# MISchematic.net
KiCad netlist of a schematic drawn in Altium Designer
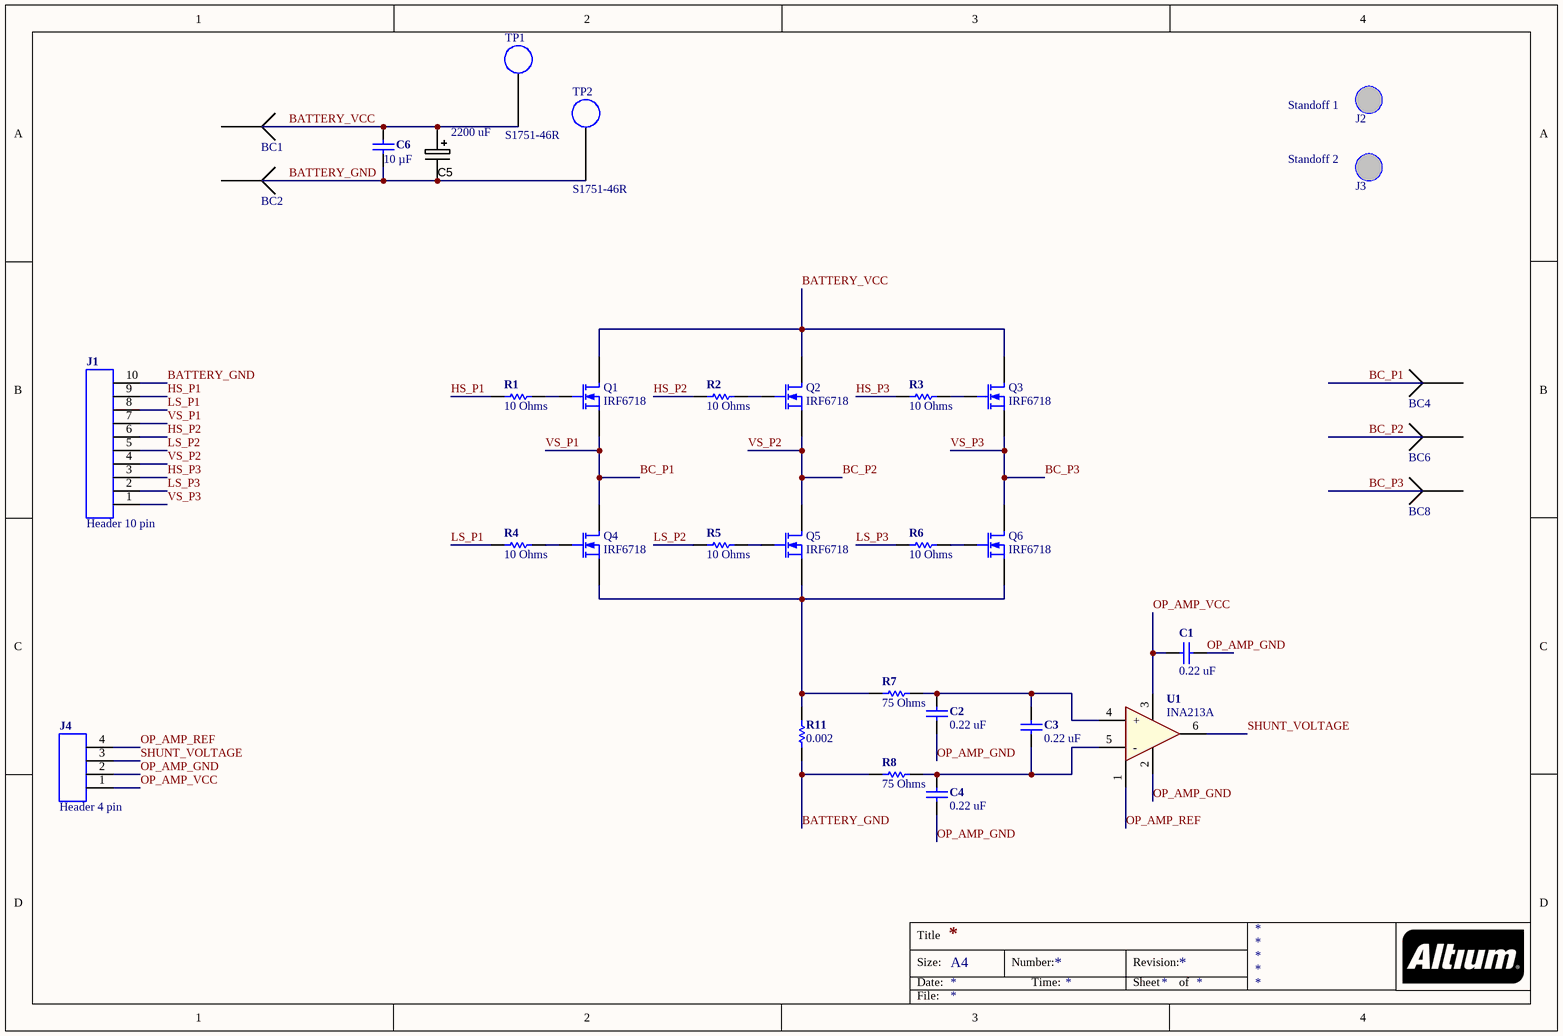
[diagram p0: MISchematic.SchDoc]

(export (version "E")
  (design (tool "Eeschema 10.0.6"))
  (components
    (comp (ref "BC1")
      (value "Bullet Connector Top")
      (footprint "BULLET_CONNECTOR_TOP")
      (description "SMD BULLET CONNECTOR")
      (libsource (lib "CarlLibrary") (part "Bullet Connector Top"))
    )
    (comp (ref "BC2")
      (value "Bullet Connector Top")
      (footprint "BULLET_CONNECTOR_TOP")
      (description "SMD BULLET CONNECTOR")
      (libsource (lib "CarlLibrary") (part "Bullet Connector Top"))
    )
    (comp (ref "BC4")
      (value "Bullet Connector Top")
      (footprint "BULLET_CONNECTOR_TOP")
      (description "SMD BULLET CONNECTOR")
      (libsource (lib "CarlLibrary") (part "Bullet Connector Top"))
    )
    (comp (ref "BC6")
      (value "Bullet Connector Top")
      (footprint "BULLET_CONNECTOR_TOP")
      (description "SMD BULLET CONNECTOR")
      (libsource (lib "CarlLibrary") (part "Bullet Connector Top"))
    )
    (comp (ref "BC8")
      (value "Bullet Connector Top")
      (footprint "BULLET_CONNECTOR_TOP")
      (description "SMD BULLET CONNECTOR")
      (libsource (lib "CarlLibrary") (part "Bullet Connector Top"))
    )
    (comp (ref "C1")
      (value "0.22 uF")
      (footprint "CAP-0805(2012)-R")
      (description "CAP CER 0.22 UF 16V 10% X7R 0805(2012)")
      (fields
        (field (name "MANUFACTURER") "Yageo")
        (field (name "MANUFACTURER PART NUMBER") "CC0805KRX7R7BB224")
      )
      (libsource (lib "CarlLibrary") (part "CAP- 0.22 uF- 16 V-CER-0805(1202)"))
    )
    (comp (ref "C2")
      (value "0.22 uF")
      (footprint "CAP-0805(2012)-R")
      (description "CAP CER 0.22 UF 16V 10% X7R 0805(2012)")
      (fields
        (field (name "MANUFACTURER") "Yageo")
        (field (name "MANUFACTURER PART NUMBER") "CC0805KRX7R7BB224")
      )
      (libsource (lib "CarlLibrary") (part "CAP- 0.22 uF- 16 V-CER-0805(1202)"))
    )
    (comp (ref "C3")
      (value "0.22 uF")
      (footprint "CAP-0805(2012)-R")
      (description "CAP CER 0.22 UF 16V 10% X7R 0805(2012)")
      (fields
        (field (name "MANUFACTURER") "Yageo")
        (field (name "MANUFACTURER PART NUMBER") "CC0805KRX7R7BB224")
      )
      (libsource (lib "CarlLibrary") (part "CAP- 0.22 uF- 16 V-CER-0805(1202)"))
    )
    (comp (ref "C4")
      (value "0.22 uF")
      (footprint "CAP-0805(2012)-R")
      (description "CAP CER 0.22 UF 16V 10% X7R 0805(2012)")
      (fields
        (field (name "MANUFACTURER") "Yageo")
        (field (name "MANUFACTURER PART NUMBER") "CC0805KRX7R7BB224")
      )
      (libsource (lib "CarlLibrary") (part "CAP- 0.22 uF- 16 V-CER-0805(1202)"))
    )
    (comp (ref "C5")
      (value "~")
      (footprint "2200uF_Rad_18x25mm")
      (description "Capacitor THT Alum Elec 2200uF 20% 50V")
      (fields (field (name "TOLERANCE") "±20%"))
      (libsource (lib "CarlLibrary") (part "CAP_2200uF_50V_THT"))
    )
    (comp (ref "C6")
      (value "10 µF")
      (footprint "CAP-1210(3225)-R")
      (description "CAP CER 10 UF 50V 10% X5R 1210")
      (fields (field (name "TOLERANCE") "±%") (field (name "MANUFACTURER") "Yageo"))
      (libsource (lib "CarlLibrary") (part "CAP- 10 uF- 50 V-CER-1210(3225)"))
    )
    (comp (ref "J1")
      (value "Header 10 pin")
      (footprint "HEADER-10-100MIL")
      (description "Header, 10pin, .1 pitch")
      (fields (field (name "MANUFACTURER") "Molex"))
      (libsource (lib "CarlLibrary") (part "CON-10Pin-100Mil"))
    )
    (comp (ref "J2")
      (value "Stand-off")
      (footprint "6-32 Threaded Standoff")
      (libsource (lib "CarlLibrary") (part "Stand-off"))
    )
    (comp (ref "J3")
      (value "Stand-off")
      (footprint "6-32 Threaded Standoff")
      (libsource (lib "CarlLibrary") (part "Stand-off"))
    )
    (comp (ref "J4")
      (value "Header 4 pin")
      (footprint "HEADER-4-100mil")
      (description "Header, 4 pin, .1 pitch")
      (libsource (lib "CarlLibrary") (part "CON-4Pin-100Mil"))
    )
    (comp (ref "Q1")
      (value "IRF6718")
      (footprint "DirectFet-7")
      (description "IRF6718L2TRPBF")
      (fields (field (name "PUBLISHER") "Altium Limited"))
      (libsource (lib "MasterLibrary") (part "IRF6718"))
    )
    (comp (ref "Q2")
      (value "IRF6718")
      (footprint "DirectFet-7")
      (description "IRF6718L2TRPBF")
      (fields (field (name "PUBLISHER") "Altium Limited"))
      (libsource (lib "MasterLibrary") (part "IRF6718"))
    )
    (comp (ref "Q3")
      (value "IRF6718")
      (footprint "DirectFet-7")
      (description "IRF6718L2TRPBF")
      (fields (field (name "PUBLISHER") "Altium Limited"))
      (libsource (lib "MasterLibrary") (part "IRF6718"))
    )
    (comp (ref "Q4")
      (value "IRF6718")
      (footprint "DirectFet-7")
      (description "IRF6718L2TRPBF")
      (fields (field (name "PUBLISHER") "Altium Limited"))
      (libsource (lib "MasterLibrary") (part "IRF6718"))
    )
    (comp (ref "Q5")
      (value "IRF6718")
      (footprint "DirectFet-7")
      (description "IRF6718L2TRPBF")
      (fields (field (name "PUBLISHER") "Altium Limited"))
      (libsource (lib "MasterLibrary") (part "IRF6718"))
    )
    (comp (ref "Q6")
      (value "IRF6718")
      (footprint "DirectFet-7")
      (description "IRF6718L2TRPBF")
      (fields (field (name "PUBLISHER") "Altium Limited"))
      (libsource (lib "MasterLibrary") (part "IRF6718"))
    )
    (comp (ref "R1")
      (value "10 Ohms")
      (footprint "R-0805(2012)-R")
      (description "RES 10 OHM 1/8W 0805 SMD")
      (fields
        (field (name "MANUFACTURER") "Yageo")
        (field (name "MANUFACTURER PART NUMBER") "RC0805FR-0710RL")
      )
      (libsource (lib "CarlLibrary") (part "R-10-125mW-0805"))
    )
    (comp (ref "R2")
      (value "10 Ohms")
      (footprint "R-0805(2012)-R")
      (description "RES 10 OHM 1/8W 0805 SMD")
      (fields
        (field (name "MANUFACTURER") "Yageo")
        (field (name "MANUFACTURER PART NUMBER") "RC0805FR-0710RL")
      )
      (libsource (lib "CarlLibrary") (part "R-10-125mW-0805"))
    )
    (comp (ref "R3")
      (value "10 Ohms")
      (footprint "R-0805(2012)-R")
      (description "RES 10 OHM 1/8W 0805 SMD")
      (fields
        (field (name "MANUFACTURER") "Yageo")
        (field (name "MANUFACTURER PART NUMBER") "RC0805FR-0710RL")
      )
      (libsource (lib "CarlLibrary") (part "R-10-125mW-0805"))
    )
    (comp (ref "R4")
      (value "10 Ohms")
      (footprint "R-0805(2012)-R")
      (description "RES 10 OHM 1/8W 0805 SMD")
      (fields
        (field (name "MANUFACTURER") "Yageo")
        (field (name "MANUFACTURER PART NUMBER") "RC0805FR-0710RL")
      )
      (libsource (lib "CarlLibrary") (part "R-10-125mW-0805"))
    )
    (comp (ref "R5")
      (value "10 Ohms")
      (footprint "R-0805(2012)-R")
      (description "RES 10 OHM 1/8W 0805 SMD")
      (fields
        (field (name "MANUFACTURER") "Yageo")
        (field (name "MANUFACTURER PART NUMBER") "RC0805FR-0710RL")
      )
      (libsource (lib "CarlLibrary") (part "R-10-125mW-0805"))
    )
    (comp (ref "R6")
      (value "10 Ohms")
      (footprint "R-0805(2012)-R")
      (description "RES 10 OHM 1/8W 0805 SMD")
      (fields
        (field (name "MANUFACTURER") "Yageo")
        (field (name "MANUFACTURER PART NUMBER") "RC0805FR-0710RL")
      )
      (libsource (lib "CarlLibrary") (part "R-10-125mW-0805"))
    )
    (comp (ref "R7")
      (value "75 Ohms")
      (footprint "R-0805(2012)-R")
      (description "RES 75OHM 125 mW 0805(2012) SMD")
      (fields
        (field (name "MANUFACTURER") "Yageo")
        (field (name "MANUFACTURER PART NUMBER") "RC0805FR-0775RL")
      )
      (libsource (lib "CarlLibrary") (part "R-75-62.5 mW-0805(2012)"))
    )
    (comp (ref "R8")
      (value "75 Ohms")
      (footprint "R-0805(2012)-R")
      (description "RES 75OHM 125 mW 0805(2012) SMD")
      (fields
        (field (name "MANUFACTURER") "Yageo")
        (field (name "MANUFACTURER PART NUMBER") "RC0805FR-0775RL")
      )
      (libsource (lib "CarlLibrary") (part "R-75-62.5 mW-0805(2012)"))
    )
    (comp (ref "R11")
      (value "0.002")
      (footprint "WSHM28182L000FEB")
      (description "RES  0.002 OHM  7W 2818(7146)-SMD")
      (fields
        (field (name "MANUFACTURER") "Vishay/Dale")
        (field (name "MANUFACTURER PART NUMBER") "WSHM28182L000FEA")
      )
      (libsource (lib "MasterLibrary") (part "WSHM28182"))
    )
    (comp (ref "TP1")
      (value "S1751-46R")
      (footprint "S1751-46R")
      (description "PC TEST POINT TIN SMD")
      (fields (field (name "MANUFACTURER") "Harwin Inc."))
      (libsource (lib "UCSD Protolab") (part "S1751-46R"))
    )
    (comp (ref "TP2")
      (value "S1751-46R")
      (footprint "S1751-46R")
      (description "PC TEST POINT TIN SMD")
      (fields (field (name "MANUFACTURER") "Harwin Inc."))
      (libsource (lib "UCSD Protolab") (part "S1751-46R"))
    )
    (comp (ref "U1")
      (value "INA213A")
      (footprint "SOT-6")
      (description "IC, OP AMP, CMOS")
      (fields (field (name "MANUFACTURER") "TI"))
      (libsource (lib "CarlLibrary") (part "OP-AMP-CURRENT-SENSE"))
    )
  )
  (nets
    (net (code "1") (name "/BATTERY_GND") (class "Default")
      (node (ref "BC2") (pin "1") (pinfunction "1_1") (pintype "passive"))
      (node (ref "C5") (pin "2") (pintype "passive"))
      (node (ref "C6") (pin "2") (pinfunction "2_2") (pintype "passive"))
      (node (ref "J1") (pin "10") (pinfunction "10_10") (pintype "passive"))
      (node (ref "R11") (pin "1") (pinfunction "1_1") (pintype "passive"))
      (node (ref "R8") (pin "1") (pinfunction "1_1") (pintype "passive"))
      (node (ref "TP2") (pin "1") (pinfunction "1_1") (pintype "passive"))
    )
    (net (code "2") (name "/BATTERY_VCC") (class "Default")
      (node (ref "BC1") (pin "1") (pinfunction "1_1") (pintype "passive"))
      (node (ref "C5") (pin "1") (pintype "passive"))
      (node (ref "C6") (pin "1") (pinfunction "1_1") (pintype "passive"))
      (node (ref "Q1") (pin "2") (pinfunction "D_2") (pintype "passive"))
      (node (ref "Q2") (pin "2") (pinfunction "D_2") (pintype "passive"))
      (node (ref "Q3") (pin "2") (pinfunction "D_2") (pintype "passive"))
      (node (ref "TP1") (pin "1") (pinfunction "1_1") (pintype "passive"))
    )
    (net (code "3") (name "/BC_P1") (class "Default")
      (node (ref "BC4") (pin "1") (pinfunction "1_1") (pintype "passive"))
      (node (ref "J1") (pin "7") (pinfunction "7_7") (pintype "passive"))
      (node (ref "Q1") (pin "3") (pinfunction "S_3") (pintype "passive"))
      (node (ref "Q4") (pin "2") (pinfunction "D_2") (pintype "passive"))
    )
    (net (code "4") (name "/BC_P2") (class "Default")
      (node (ref "BC6") (pin "1") (pinfunction "1_1") (pintype "passive"))
      (node (ref "J1") (pin "4") (pinfunction "4_4") (pintype "passive"))
      (node (ref "Q2") (pin "3") (pinfunction "S_3") (pintype "passive"))
      (node (ref "Q5") (pin "2") (pinfunction "D_2") (pintype "passive"))
    )
    (net (code "5") (name "/BC_P3") (class "Default")
      (node (ref "BC8") (pin "1") (pinfunction "1_1") (pintype "passive"))
      (node (ref "J1") (pin "1") (pinfunction "1_1") (pintype "passive"))
      (node (ref "Q3") (pin "3") (pinfunction "S_3") (pintype "passive"))
      (node (ref "Q6") (pin "2") (pinfunction "D_2") (pintype "passive"))
    )
    (net (code "6") (name "/HS_P1") (class "Default")
      (node (ref "J1") (pin "9") (pinfunction "9_9") (pintype "passive"))
      (node (ref "R1") (pin "2") (pinfunction "2_2") (pintype "passive"))
    )
    (net (code "7") (name "/HS_P2") (class "Default")
      (node (ref "J1") (pin "6") (pinfunction "6_6") (pintype "passive"))
      (node (ref "R2") (pin "2") (pinfunction "2_2") (pintype "passive"))
    )
    (net (code "8") (name "/HS_P3") (class "Default")
      (node (ref "J1") (pin "3") (pinfunction "3_3") (pintype "passive"))
      (node (ref "R3") (pin "2") (pinfunction "2_2") (pintype "passive"))
    )
    (net (code "9") (name "/LS_P1") (class "Default")
      (node (ref "J1") (pin "8") (pinfunction "8_8") (pintype "passive"))
      (node (ref "R4") (pin "2") (pinfunction "2_2") (pintype "passive"))
    )
    (net (code "10") (name "/LS_P2") (class "Default")
      (node (ref "J1") (pin "5") (pinfunction "5_5") (pintype "passive"))
      (node (ref "R5") (pin "2") (pinfunction "2_2") (pintype "passive"))
    )
    (net (code "11") (name "/LS_P3") (class "Default")
      (node (ref "J1") (pin "2") (pinfunction "2_2") (pintype "passive"))
      (node (ref "R6") (pin "2") (pinfunction "2_2") (pintype "passive"))
    )
    (net (code "12") (name "/OP_AMP_GND") (class "Default")
      (node (ref "C1") (pin "2") (pinfunction "2_2") (pintype "passive"))
      (node (ref "C2") (pin "2") (pinfunction "2_2") (pintype "passive"))
      (node (ref "C4") (pin "2") (pinfunction "2_2") (pintype "passive"))
      (node (ref "J4") (pin "2") (pinfunction "2_2") (pintype "passive"))
      (node (ref "U1") (pin "2") (pinfunction "GND_2") (pintype "power_in"))
    )
    (net (code "13") (name "/OP_AMP_REF") (class "Default")
      (node (ref "J4") (pin "4") (pinfunction "4_4") (pintype "passive"))
      (node (ref "U1") (pin "1") (pinfunction "REF_1") (pintype "power_in"))
    )
    (net (code "14") (name "/OP_AMP_VCC") (class "Default")
      (node (ref "C1") (pin "1") (pinfunction "1_1") (pintype "passive"))
      (node (ref "J4") (pin "1") (pinfunction "1_1") (pintype "passive"))
      (node (ref "U1") (pin "3") (pinfunction "VCC_3") (pintype "power_in"))
    )
    (net (code "15") (name "/SHUNT_VOLTAGE") (class "Default")
      (node (ref "J4") (pin "3") (pinfunction "3_3") (pintype "passive"))
      (node (ref "U1") (pin "6") (pinfunction "OUT_6") (pintype "passive"))
    )
    (net (code "16") (name "Net-(Q1-G)") (class "Default")
      (node (ref "Q1") (pin "1") (pinfunction "G_1") (pintype "passive"))
      (node (ref "R1") (pin "1") (pinfunction "1_1") (pintype "passive"))
    )
    (net (code "17") (name "Net-(Q2-G)") (class "Default")
      (node (ref "Q2") (pin "1") (pinfunction "G_1") (pintype "passive"))
      (node (ref "R2") (pin "1") (pinfunction "1_1") (pintype "passive"))
    )
    (net (code "18") (name "Net-(Q3-G)") (class "Default")
      (node (ref "Q3") (pin "1") (pinfunction "G_1") (pintype "passive"))
      (node (ref "R3") (pin "1") (pinfunction "1_1") (pintype "passive"))
    )
    (net (code "19") (name "Net-(Q4-G)") (class "Default")
      (node (ref "Q4") (pin "1") (pinfunction "G_1") (pintype "passive"))
      (node (ref "R4") (pin "1") (pinfunction "1_1") (pintype "passive"))
    )
    (net (code "20") (name "Net-(Q4-S)") (class "Default")
      (node (ref "Q4") (pin "3") (pinfunction "S_3") (pintype "passive"))
      (node (ref "Q5") (pin "3") (pinfunction "S_3") (pintype "passive"))
      (node (ref "Q6") (pin "3") (pinfunction "S_3") (pintype "passive"))
      (node (ref "R11") (pin "2") (pinfunction "2_2") (pintype "passive"))
      (node (ref "R7") (pin "1") (pinfunction "1_1") (pintype "passive"))
    )
    (net (code "21") (name "Net-(Q5-G)") (class "Default")
      (node (ref "Q5") (pin "1") (pinfunction "G_1") (pintype "passive"))
      (node (ref "R5") (pin "1") (pinfunction "1_1") (pintype "passive"))
    )
    (net (code "22") (name "Net-(Q6-G)") (class "Default")
      (node (ref "Q6") (pin "1") (pinfunction "G_1") (pintype "passive"))
      (node (ref "R6") (pin "1") (pinfunction "1_1") (pintype "passive"))
    )
    (net (code "23") (name "Net-(U1-+)") (class "Default")
      (node (ref "C2") (pin "1") (pinfunction "1_1") (pintype "passive"))
      (node (ref "C3") (pin "1") (pinfunction "1_1") (pintype "passive"))
      (node (ref "R7") (pin "2") (pinfunction "2_2") (pintype "passive"))
      (node (ref "U1") (pin "4") (pinfunction "+_4") (pintype "passive"))
    )
    (net (code "24") (name "Net-(U1--)") (class "Default")
      (node (ref "C3") (pin "2") (pinfunction "2_2") (pintype "passive"))
      (node (ref "C4") (pin "1") (pinfunction "1_1") (pintype "passive"))
      (node (ref "R8") (pin "2") (pinfunction "2_2") (pintype "passive"))
      (node (ref "U1") (pin "5") (pinfunction "-_5") (pintype "passive"))
    )
  )
)
